# prog_jig_controller_v1.net
KiCad netlist of a schematic drawn in EAGLE
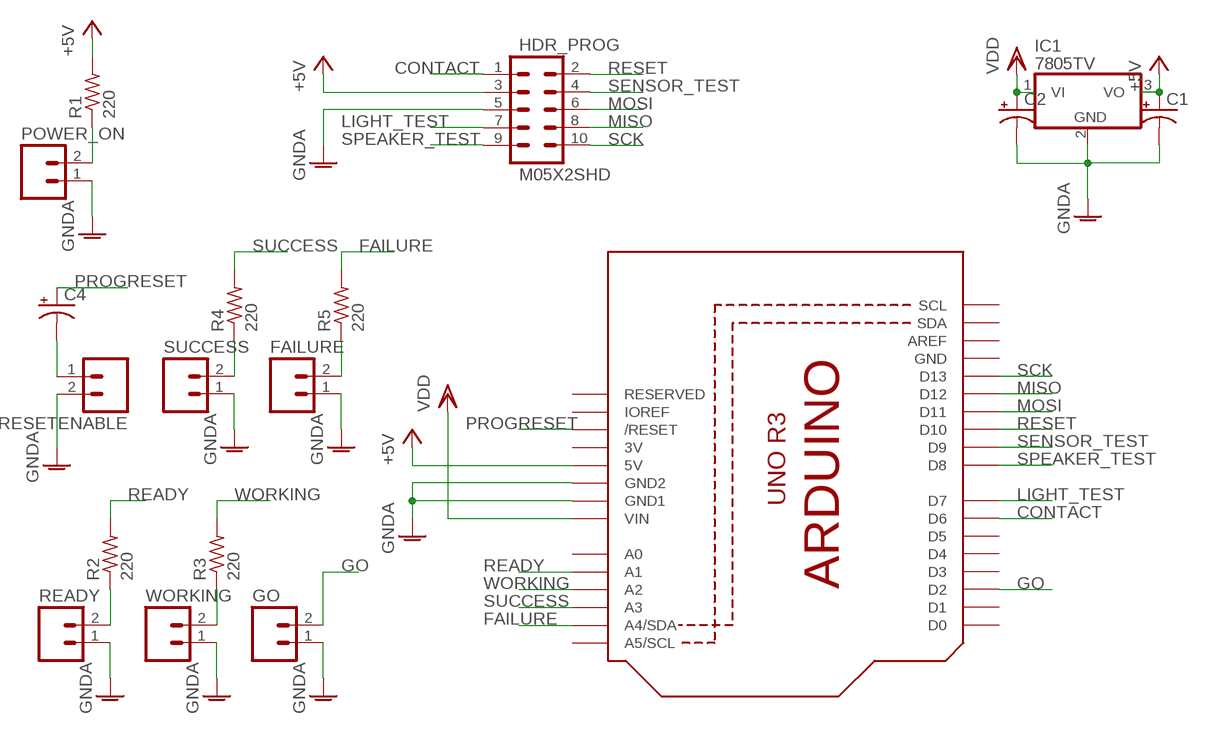
[diagram p0: schematic, sheet 1]

(export (version "E")
  (design (tool "Eeschema 10.0.6"))
  (components
    (comp (ref "C1")
      (value "CAP_POLPTH2")
      (footprint "eagle-import:CPOL-RADIAL-10UF-25V")
      (libsource (lib "eagle-import") (part "CAP_POLPTH2"))
    )
    (comp (ref "C2")
      (value "CAP_POLPTH2")
      (footprint "eagle-import:CPOL-RADIAL-10UF-25V")
      (libsource (lib "eagle-import") (part "CAP_POLPTH2"))
    )
    (comp (ref "C4")
      (value "CAP_POLPTH2")
      (footprint "eagle-import:CPOL-RADIAL-10UF-25V")
      (libsource (lib "eagle-import") (part "CAP_POLPTH2"))
    )
    (comp (ref "FAILURE")
      (value "M02JST-PTH-2")
      (footprint "eagle-import:JST-2-PTH")
      (libsource (lib "eagle-import") (part "M02JST-PTH-2"))
    )
    (comp (ref "GO")
      (value "M02JST-PTH-2")
      (footprint "eagle-import:JST-2-PTH")
      (libsource (lib "eagle-import") (part "M02JST-PTH-2"))
    )
    (comp (ref "HDR_PROG")
      (value "M05X2SHD")
      (footprint "eagle-import:2X5-SHROUDED")
      (libsource (lib "eagle-import") (part "M05X2SHD"))
    )
    (comp (ref "IC1")
      (value "7805TV")
      (footprint "eagle-import:TO220V")
      (libsource (lib "eagle-import") (part "78TV05"))
    )
    (comp (ref "POWER_ON")
      (value "M02JST-PTH-2")
      (footprint "eagle-import:JST-2-PTH")
      (libsource (lib "eagle-import") (part "M02JST-PTH-2"))
    )
    (comp (ref "R1")
      (value "220")
      (footprint "eagle-import:0204_7")
      (libsource (lib "eagle-import") (part "R-US_0204/7"))
    )
    (comp (ref "R2")
      (value "220")
      (footprint "eagle-import:0204_7")
      (libsource (lib "eagle-import") (part "R-US_0204/7"))
    )
    (comp (ref "R3")
      (value "220")
      (footprint "eagle-import:0204_7")
      (libsource (lib "eagle-import") (part "R-US_0204/7"))
    )
    (comp (ref "R4")
      (value "220")
      (footprint "eagle-import:0204_7")
      (libsource (lib "eagle-import") (part "R-US_0204/7"))
    )
    (comp (ref "R5")
      (value "220")
      (footprint "eagle-import:0204_7")
      (libsource (lib "eagle-import") (part "R-US_0204/7"))
    )
    (comp (ref "READY")
      (value "M02JST-PTH-2")
      (footprint "eagle-import:JST-2-PTH")
      (libsource (lib "eagle-import") (part "M02JST-PTH-2"))
    )
    (comp (ref "RESETENABLE")
      (value "M02JST-PTH-2")
      (footprint "eagle-import:JST-2-PTH")
      (libsource (lib "eagle-import") (part "M02JST-PTH-2"))
    )
    (comp (ref "SUCCESS")
      (value "M02JST-PTH-2")
      (footprint "eagle-import:JST-2-PTH")
      (libsource (lib "eagle-import") (part "M02JST-PTH-2"))
    )
    (comp (ref "U1")
      (value "ARDUINOR3-DIMENSION")
      (footprint "eagle-import:ARDUINOR3")
      (libsource (lib "eagle-import") (part "ARDUINOR3-DIMENSION"))
    )
    (comp (ref "WORKING")
      (value "M02JST-PTH-2")
      (footprint "eagle-import:JST-2-PTH")
      (libsource (lib "eagle-import") (part "M02JST-PTH-2"))
    )
  )
  (nets
    (net (code "1") (name "+5V") (class "Default")
      (node (ref "C1") (pin "1") (pinfunction "+_1") (pintype "passive"))
      (node (ref "HDR_PROG") (pin "3") (pinfunction "3_3") (pintype "passive"))
      (node (ref "IC1") (pin "3") (pinfunction "VO_3") (pintype "passive"))
      (node (ref "R1") (pin "2") (pinfunction "2_2") (pintype "passive"))
      (node (ref "U1") (pin "5V") (pinfunction "5V_5V") (pintype "power_in"))
    )
    (net (code "2") (name "/3V") (class "Default")
      (node (ref "U1") (pin "3V") (pinfunction "3V_3V") (pintype "power_in"))
    )
    (net (code "3") (name "/CONTACT") (class "Default")
      (node (ref "HDR_PROG") (pin "1") (pinfunction "1_1") (pintype "passive"))
      (node (ref "U1") (pin "D6") (pinfunction "D6_D6") (pintype "bidirectional"))
    )
    (net (code "4") (name "/FAILURE") (class "Default")
      (node (ref "R5") (pin "2") (pinfunction "2_2") (pintype "passive"))
      (node (ref "U1") (pin "A4") (pinfunction "A4/SDA_A4") (pintype "bidirectional"))
    )
    (net (code "5") (name "/GND") (class "Default")
      (node (ref "U1") (pin "GND") (pinfunction "GND_GND") (pintype "power_in"))
    )
    (net (code "6") (name "/GO") (class "Default")
      (node (ref "GO") (pin "2") (pinfunction "2_2") (pintype "passive"))
      (node (ref "U1") (pin "D2") (pinfunction "D2_D2") (pintype "bidirectional"))
    )
    (net (code "7") (name "/LIGHT_TEST") (class "Default")
      (node (ref "HDR_PROG") (pin "7") (pinfunction "7_7") (pintype "passive"))
      (node (ref "U1") (pin "D7") (pinfunction "D7_D7") (pintype "bidirectional"))
    )
    (net (code "8") (name "/MISO") (class "Default")
      (node (ref "HDR_PROG") (pin "8") (pinfunction "8_8") (pintype "passive"))
      (node (ref "U1") (pin "D12") (pinfunction "D12_D12") (pintype "bidirectional"))
    )
    (net (code "9") (name "/MOSI") (class "Default")
      (node (ref "HDR_PROG") (pin "6") (pinfunction "6_6") (pintype "passive"))
      (node (ref "U1") (pin "D11") (pinfunction "D11_D11") (pintype "bidirectional"))
    )
    (net (code "10") (name "/PROGRESET") (class "Default")
      (node (ref "C4") (pin "1") (pinfunction "+_1") (pintype "passive"))
      (node (ref "U1") (pin "RESET") (pinfunction "/RESET_RESET") (pintype "bidirectional"))
    )
    (net (code "11") (name "/READY") (class "Default")
      (node (ref "R2") (pin "2") (pinfunction "2_2") (pintype "passive"))
      (node (ref "U1") (pin "A1") (pinfunction "A1_A1") (pintype "bidirectional"))
    )
    (net (code "12") (name "/RESET") (class "Default")
      (node (ref "HDR_PROG") (pin "2") (pinfunction "2_2") (pintype "passive"))
      (node (ref "U1") (pin "D10") (pinfunction "D10_D10") (pintype "bidirectional"))
    )
    (net (code "13") (name "/SCK") (class "Default")
      (node (ref "HDR_PROG") (pin "10") (pinfunction "10_10") (pintype "passive"))
      (node (ref "U1") (pin "D13") (pinfunction "D13_D13") (pintype "bidirectional"))
    )
    (net (code "14") (name "/SENSOR_TEST") (class "Default")
      (node (ref "HDR_PROG") (pin "4") (pinfunction "4_4") (pintype "passive"))
      (node (ref "U1") (pin "D9") (pinfunction "D9_D9") (pintype "bidirectional"))
    )
    (net (code "15") (name "/SPEAKER_TEST") (class "Default")
      (node (ref "HDR_PROG") (pin "9") (pinfunction "9_9") (pintype "passive"))
      (node (ref "U1") (pin "D8") (pinfunction "D8_D8") (pintype "bidirectional"))
    )
    (net (code "16") (name "/SUCCESS") (class "Default")
      (node (ref "R4") (pin "2") (pinfunction "2_2") (pintype "passive"))
      (node (ref "U1") (pin "A3") (pinfunction "A3_A3") (pintype "bidirectional"))
    )
    (net (code "17") (name "/WORKING") (class "Default")
      (node (ref "R3") (pin "2") (pinfunction "2_2") (pintype "passive"))
      (node (ref "U1") (pin "A2") (pinfunction "A2_A2") (pintype "bidirectional"))
    )
    (net (code "18") (name "GNDA") (class "Default")
      (node (ref "C1") (pin "2") (pinfunction "-_2") (pintype "passive"))
      (node (ref "C2") (pin "2") (pinfunction "-_2") (pintype "passive"))
      (node (ref "FAILURE") (pin "1") (pinfunction "1_1") (pintype "passive"))
      (node (ref "GO") (pin "1") (pinfunction "1_1") (pintype "passive"))
      (node (ref "HDR_PROG") (pin "5") (pinfunction "5_5") (pintype "passive"))
      (node (ref "IC1") (pin "2") (pinfunction "GND_2") (pintype "passive"))
      (node (ref "POWER_ON") (pin "1") (pinfunction "1_1") (pintype "passive"))
      (node (ref "READY") (pin "1") (pinfunction "1_1") (pintype "passive"))
      (node (ref "RESETENABLE") (pin "2") (pinfunction "2_2") (pintype "passive"))
      (node (ref "SUCCESS") (pin "1") (pinfunction "1_1") (pintype "passive"))
      (node (ref "U1") (pin "GND1") (pinfunction "GND1_GND1") (pintype "power_in"))
      (node (ref "U1") (pin "GND2") (pinfunction "GND2_GND2") (pintype "power_in"))
      (node (ref "WORKING") (pin "1") (pinfunction "1_1") (pintype "passive"))
    )
    (net (code "19") (name "Net-(C4--)") (class "Default")
      (node (ref "C4") (pin "2") (pinfunction "-_2") (pintype "passive"))
      (node (ref "RESETENABLE") (pin "1") (pinfunction "1_1") (pintype "passive"))
    )
    (net (code "20") (name "Net-(FAILURE-Pad2)") (class "Default")
      (node (ref "FAILURE") (pin "2") (pinfunction "2_2") (pintype "passive"))
      (node (ref "R5") (pin "1") (pinfunction "1_1") (pintype "passive"))
    )
    (net (code "21") (name "Net-(POWER_ON-Pad2)") (class "Default")
      (node (ref "POWER_ON") (pin "2") (pinfunction "2_2") (pintype "passive"))
      (node (ref "R1") (pin "1") (pinfunction "1_1") (pintype "passive"))
    )
    (net (code "22") (name "Net-(R2-Pad1)") (class "Default")
      (node (ref "R2") (pin "1") (pinfunction "1_1") (pintype "passive"))
      (node (ref "READY") (pin "2") (pinfunction "2_2") (pintype "passive"))
    )
    (net (code "23") (name "Net-(R3-Pad1)") (class "Default")
      (node (ref "R3") (pin "1") (pinfunction "1_1") (pintype "passive"))
      (node (ref "WORKING") (pin "2") (pinfunction "2_2") (pintype "passive"))
    )
    (net (code "24") (name "Net-(R4-Pad1)") (class "Default")
      (node (ref "R4") (pin "1") (pinfunction "1_1") (pintype "passive"))
      (node (ref "SUCCESS") (pin "2") (pinfunction "2_2") (pintype "passive"))
    )
    (net (code "25") (name "VDD") (class "Default")
      (node (ref "C2") (pin "1") (pinfunction "+_1") (pintype "passive"))
      (node (ref "IC1") (pin "1") (pinfunction "VI_1") (pintype "input"))
      (node (ref "U1") (pin "VIN") (pinfunction "VIN_VIN") (pintype "power_in"))
    )
    (net (code "26") (name "unconnected-(U1-A5{slash}SCL-PadA5)") (class "Default")
      (node (ref "U1") (pin "A5") (pinfunction "A5/SCL_A5") (pintype "bidirectional"))
    )
    (net (code "27") (name "unconnected-(U1-PadA0)") (class "Default")
      (node (ref "U1") (pin "A0") (pinfunction "A0_A0") (pintype "bidirectional"))
    )
    (net (code "28") (name "unconnected-(U1-PadAREF)") (class "Default")
      (node (ref "U1") (pin "AREF") (pinfunction "AREF_AREF") (pintype "bidirectional"))
    )
    (net (code "29") (name "unconnected-(U1-PadD0)") (class "Default")
      (node (ref "U1") (pin "D0") (pinfunction "D0_D0") (pintype "bidirectional"))
    )
    (net (code "30") (name "unconnected-(U1-PadD1)") (class "Default")
      (node (ref "U1") (pin "D1") (pinfunction "D1_D1") (pintype "bidirectional"))
    )
    (net (code "31") (name "unconnected-(U1-PadD3)") (class "Default")
      (node (ref "U1") (pin "D3") (pinfunction "D3_D3") (pintype "bidirectional"))
    )
    (net (code "32") (name "unconnected-(U1-PadD4)") (class "Default")
      (node (ref "U1") (pin "D4") (pinfunction "D4_D4") (pintype "bidirectional"))
    )
    (net (code "33") (name "unconnected-(U1-PadD5)") (class "Default")
      (node (ref "U1") (pin "D5") (pinfunction "D5_D5") (pintype "bidirectional"))
    )
    (net (code "34") (name "unconnected-(U1-PadIOREF)") (class "Default")
      (node (ref "U1") (pin "IOREF") (pinfunction "IOREF_IOREF") (pintype "output"))
    )
    (net (code "35") (name "unconnected-(U1-PadRESERVED)") (class "Default")
      (node (ref "U1") (pin "RESERVED") (pinfunction "RESERVED_RESERVED") (pintype "no_connect"))
    )
    (net (code "36") (name "unconnected-(U1-PadSCL)") (class "Default")
      (node (ref "U1") (pin "SCL") (pinfunction "SCL_SCL") (pintype "bidirectional"))
    )
    (net (code "37") (name "unconnected-(U1-PadSDA)") (class "Default")
      (node (ref "U1") (pin "SDA") (pinfunction "SDA_SDA") (pintype "bidirectional"))
    )
  )
)
